# InstAmp.net
KiCad netlist of a schematic drawn in EAGLE
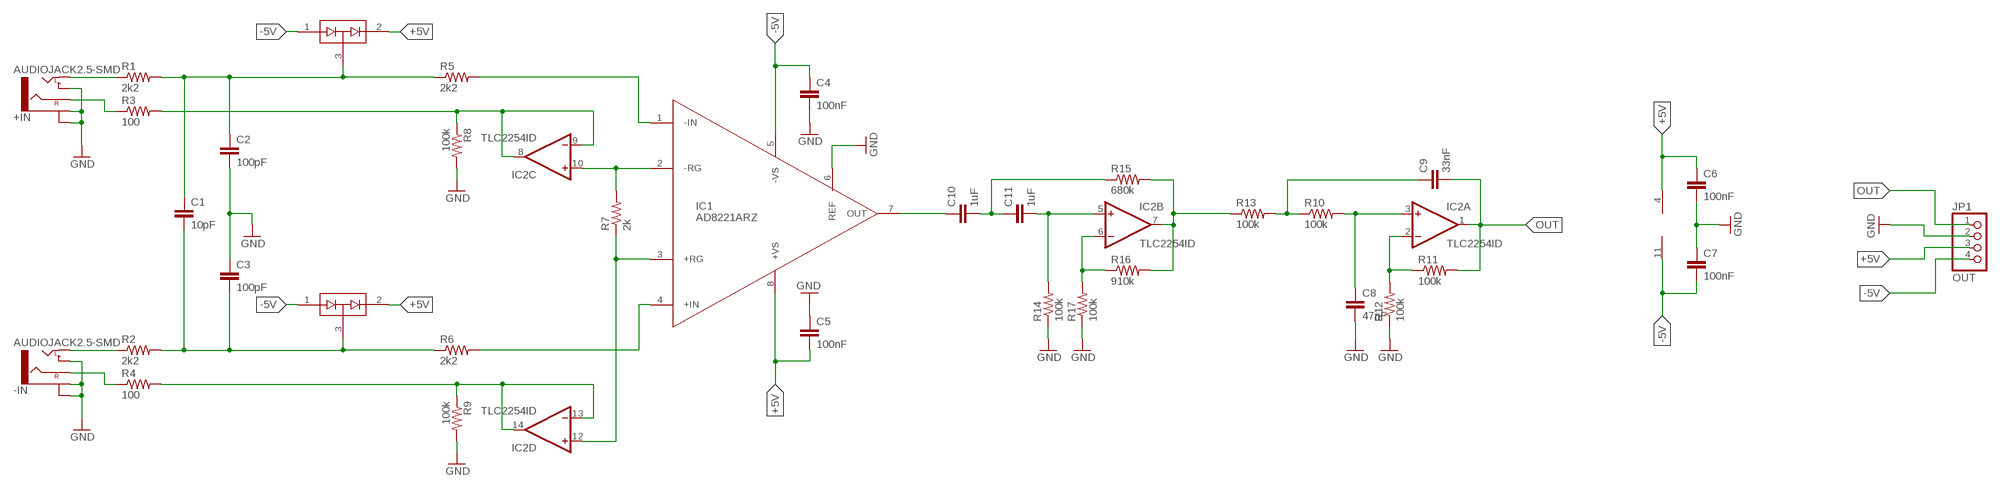
[diagram p0: schematic, sheet 1]

(export (version "E")
  (design (tool "Eeschema 10.0.6"))
  (components
    (comp (ref "+IN")
      (value "AUDIOJACK2.5-SMD")
      (footprint "eagle-import:AUDIOJACK2.5-SMD")
      (libsource (lib "eagle-import") (part "AUDIOJACK2.5-SMD"))
    )
    (comp (ref "-IN")
      (value "AUDIOJACK2.5-SMD")
      (footprint "eagle-import:AUDIOJACK2.5-SMD")
      (libsource (lib "eagle-import") (part "AUDIOJACK2.5-SMD"))
    )
    (comp (ref "C1")
      (value "10pF")
      (footprint "eagle-import:0805")
      (libsource (lib "eagle-import") (part "CAP0805"))
    )
    (comp (ref "C2")
      (value "100pF")
      (footprint "eagle-import:0805")
      (libsource (lib "eagle-import") (part "CAP0805"))
    )
    (comp (ref "C3")
      (value "100pF")
      (footprint "eagle-import:0805")
      (libsource (lib "eagle-import") (part "CAP0805"))
    )
    (comp (ref "C4")
      (value "100nF")
      (footprint "eagle-import:0805")
      (libsource (lib "eagle-import") (part "CAP0805"))
    )
    (comp (ref "C5")
      (value "100nF")
      (footprint "eagle-import:0805")
      (libsource (lib "eagle-import") (part "CAP0805"))
    )
    (comp (ref "C6")
      (value "100nF")
      (footprint "eagle-import:0805")
      (libsource (lib "eagle-import") (part "CAP0805"))
    )
    (comp (ref "C7")
      (value "100nF")
      (footprint "eagle-import:0805")
      (libsource (lib "eagle-import") (part "CAP0805"))
    )
    (comp (ref "C8")
      (value "47nF")
      (footprint "eagle-import:0805")
      (libsource (lib "eagle-import") (part "CAP0805"))
    )
    (comp (ref "C9")
      (value "33nF")
      (footprint "eagle-import:0805")
      (libsource (lib "eagle-import") (part "CAP0805"))
    )
    (comp (ref "C10")
      (value "1uF")
      (footprint "eagle-import:0805")
      (libsource (lib "eagle-import") (part "CAP0805"))
    )
    (comp (ref "C11")
      (value "1uF")
      (footprint "eagle-import:0805")
      (libsource (lib "eagle-import") (part "CAP0805"))
    )
    (comp (ref "D1")
      (value "BAV199")
      (footprint "eagle-import:SOT23")
      (fields (field (name "PROD_ID") "DIO-10647"))
      (libsource (lib "eagle-import") (part "BAV99"))
    )
    (comp (ref "D2")
      (value "BAV199")
      (footprint "eagle-import:SOT23")
      (libsource (lib "eagle-import") (part "BAV99"))
    )
    (comp (ref "IC1")
      (value "AD8221ARZ")
      (footprint "eagle-import:AD8221ARZ")
      (libsource (lib "eagle-import") (part "AD8221ARZ"))
    )
    (comp (ref "IC2")
      (value "TLC2254ID")
      (footprint "eagle-import:SO14")
      (libsource (lib "eagle-import") (part "4AMP_P4+11D"))
    )
    (comp (ref "JP1")
      (value "OUT")
      (footprint "eagle-import:1X04_90")
      (libsource (lib "eagle-import") (part "PINHD-1X4/90"))
    )
    (comp (ref "R1")
      (value "2k2")
      (footprint "eagle-import:0805")
      (libsource (lib "eagle-import") (part "RESISTOR0805-RES"))
    )
    (comp (ref "R2")
      (value "2k2")
      (footprint "eagle-import:0805")
      (libsource (lib "eagle-import") (part "RESISTOR0805-RES"))
    )
    (comp (ref "R3")
      (value "100")
      (footprint "eagle-import:0805")
      (libsource (lib "eagle-import") (part "RESISTOR0805-RES"))
    )
    (comp (ref "R4")
      (value "100")
      (footprint "eagle-import:0805")
      (libsource (lib "eagle-import") (part "RESISTOR0805-RES"))
    )
    (comp (ref "R5")
      (value "2k2")
      (footprint "eagle-import:0805")
      (libsource (lib "eagle-import") (part "RESISTOR0805-RES"))
    )
    (comp (ref "R6")
      (value "2k2")
      (footprint "eagle-import:0805")
      (libsource (lib "eagle-import") (part "RESISTOR0805-RES"))
    )
    (comp (ref "R7")
      (value "2k")
      (footprint "eagle-import:0805")
      (libsource (lib "eagle-import") (part "RESISTOR0805-RES"))
    )
    (comp (ref "R8")
      (value "100k")
      (footprint "eagle-import:0805")
      (libsource (lib "eagle-import") (part "RESISTOR0805-RES"))
    )
    (comp (ref "R9")
      (value "100k")
      (footprint "eagle-import:0805")
      (libsource (lib "eagle-import") (part "RESISTOR0805-RES"))
    )
    (comp (ref "R10")
      (value "100k")
      (footprint "eagle-import:0805")
      (libsource (lib "eagle-import") (part "RESISTOR0805-RES"))
    )
    (comp (ref "R11")
      (value "100k")
      (footprint "eagle-import:0805")
      (libsource (lib "eagle-import") (part "RESISTOR0805-RES"))
    )
    (comp (ref "R12")
      (value "100k")
      (footprint "eagle-import:0805")
      (libsource (lib "eagle-import") (part "RESISTOR0805-RES"))
    )
    (comp (ref "R13")
      (value "100k")
      (footprint "eagle-import:0805")
      (libsource (lib "eagle-import") (part "RESISTOR0805-RES"))
    )
    (comp (ref "R14")
      (value "100k")
      (footprint "eagle-import:0805")
      (libsource (lib "eagle-import") (part "RESISTOR0805-RES"))
    )
    (comp (ref "R15")
      (value "680k")
      (footprint "eagle-import:0805")
      (libsource (lib "eagle-import") (part "RESISTOR0805-RES"))
    )
    (comp (ref "R16")
      (value "910k")
      (footprint "eagle-import:0805")
      (libsource (lib "eagle-import") (part "RESISTOR0805-RES"))
    )
    (comp (ref "R17")
      (value "100k")
      (footprint "eagle-import:0805")
      (libsource (lib "eagle-import") (part "RESISTOR0805-RES"))
    )
  )
  (nets
    (net (code "1") (name "+5V") (class "Default")
      (node (ref "C5") (pin "2") (pinfunction "2_2") (pintype "passive"))
      (node (ref "C6") (pin "1") (pinfunction "1_1") (pintype "passive"))
      (node (ref "D1") (pin "2") (pinfunction "C2_2") (pintype "bidirectional"))
      (node (ref "D2") (pin "2") (pinfunction "C2_2") (pintype "bidirectional"))
      (node (ref "IC1") (pin "8") (pinfunction "+VS_8") (pintype "power_in"))
      (node (ref "IC2") (pin "4") (pinfunction "V+_4") (pintype "power_in"))
      (node (ref "JP1") (pin "3") (pinfunction "3_3") (pintype "passive"))
    )
    (net (code "2") (name "-5V") (class "Default")
      (node (ref "C4") (pin "1") (pinfunction "1_1") (pintype "passive"))
      (node (ref "C7") (pin "2") (pinfunction "2_2") (pintype "passive"))
      (node (ref "D1") (pin "1") (pinfunction "A1_1") (pintype "bidirectional"))
      (node (ref "D2") (pin "1") (pinfunction "A1_1") (pintype "bidirectional"))
      (node (ref "IC1") (pin "5") (pinfunction "-VS_5") (pintype "power_in"))
      (node (ref "IC2") (pin "11") (pinfunction "V-_11") (pintype "power_in"))
      (node (ref "JP1") (pin "4") (pinfunction "4_4") (pintype "passive"))
    )
    (net (code "3") (name "GND") (class "Default")
      (node (ref "+IN") (pin "GND1") (pinfunction "GND1_GND1") (pintype "bidirectional"))
      (node (ref "+IN") (pin "GND2") (pinfunction "GND2_GND2") (pintype "bidirectional"))
      (node (ref "+IN") (pin "SW") (pinfunction "SW_SW") (pintype "bidirectional"))
      (node (ref "-IN") (pin "GND1") (pinfunction "GND1_GND1") (pintype "bidirectional"))
      (node (ref "-IN") (pin "GND2") (pinfunction "GND2_GND2") (pintype "bidirectional"))
      (node (ref "-IN") (pin "SW") (pinfunction "SW_SW") (pintype "bidirectional"))
      (node (ref "C2") (pin "2") (pinfunction "2_2") (pintype "passive"))
      (node (ref "C3") (pin "1") (pinfunction "1_1") (pintype "passive"))
      (node (ref "C4") (pin "2") (pinfunction "2_2") (pintype "passive"))
      (node (ref "C5") (pin "1") (pinfunction "1_1") (pintype "passive"))
      (node (ref "C6") (pin "2") (pinfunction "2_2") (pintype "passive"))
      (node (ref "C7") (pin "1") (pinfunction "1_1") (pintype "passive"))
      (node (ref "C8") (pin "2") (pinfunction "2_2") (pintype "passive"))
      (node (ref "IC1") (pin "6") (pinfunction "REF_6") (pintype "bidirectional"))
      (node (ref "JP1") (pin "2") (pinfunction "2_2") (pintype "passive"))
      (node (ref "R12") (pin "1") (pinfunction "1_1") (pintype "passive"))
      (node (ref "R14") (pin "1") (pinfunction "1_1") (pintype "passive"))
      (node (ref "R17") (pin "1") (pinfunction "1_1") (pintype "passive"))
      (node (ref "R8") (pin "2") (pinfunction "2_2") (pintype "passive"))
      (node (ref "R9") (pin "2") (pinfunction "2_2") (pintype "passive"))
    )
    (net (code "4") (name "Net-(+IN-LEFT)") (class "Default")
      (node (ref "+IN") (pin "L") (pinfunction "LEFT_L") (pintype "bidirectional"))
      (node (ref "R1") (pin "1") (pinfunction "1_1") (pintype "passive"))
    )
    (net (code "5") (name "Net-(+IN-RIGHT)") (class "Default")
      (node (ref "+IN") (pin "R") (pinfunction "RIGHT_R") (pintype "bidirectional"))
      (node (ref "R3") (pin "1") (pinfunction "1_1") (pintype "passive"))
    )
    (net (code "6") (name "Net-(-IN-LEFT)") (class "Default")
      (node (ref "-IN") (pin "L") (pinfunction "LEFT_L") (pintype "bidirectional"))
      (node (ref "R2") (pin "1") (pinfunction "1_1") (pintype "passive"))
    )
    (net (code "7") (name "Net-(-IN-RIGHT)") (class "Default")
      (node (ref "-IN") (pin "R") (pinfunction "RIGHT_R") (pintype "bidirectional"))
      (node (ref "R4") (pin "1") (pinfunction "1_1") (pintype "passive"))
    )
    (net (code "8") (name "Net-(C9-Pad1)") (class "Default")
      (node (ref "C9") (pin "1") (pinfunction "1_1") (pintype "passive"))
      (node (ref "R10") (pin "1") (pinfunction "1_1") (pintype "passive"))
      (node (ref "R13") (pin "2") (pinfunction "2_2") (pintype "passive"))
    )
    (net (code "9") (name "Net-(C10-Pad2)") (class "Default")
      (node (ref "C10") (pin "2") (pinfunction "2_2") (pintype "passive"))
      (node (ref "C11") (pin "1") (pinfunction "1_1") (pintype "passive"))
      (node (ref "R15") (pin "1") (pinfunction "1_1") (pintype "passive"))
    )
    (net (code "10") (name "Net-(D1-COM)") (class "Default")
      (node (ref "C1") (pin "1") (pinfunction "1_1") (pintype "passive"))
      (node (ref "C2") (pin "1") (pinfunction "1_1") (pintype "passive"))
      (node (ref "D1") (pin "3") (pinfunction "COM_3") (pintype "bidirectional"))
      (node (ref "R1") (pin "2") (pinfunction "2_2") (pintype "passive"))
      (node (ref "R5") (pin "1") (pinfunction "1_1") (pintype "passive"))
    )
    (net (code "11") (name "Net-(D2-COM)") (class "Default")
      (node (ref "C1") (pin "2") (pinfunction "2_2") (pintype "passive"))
      (node (ref "C3") (pin "2") (pinfunction "2_2") (pintype "passive"))
      (node (ref "D2") (pin "3") (pinfunction "COM_3") (pintype "bidirectional"))
      (node (ref "R2") (pin "2") (pinfunction "2_2") (pintype "passive"))
      (node (ref "R6") (pin "1") (pinfunction "1_1") (pintype "passive"))
    )
    (net (code "12") (name "Net-(IC1-+IN)") (class "Default")
      (node (ref "IC1") (pin "4") (pinfunction "+IN_4") (pintype "bidirectional"))
      (node (ref "R6") (pin "2") (pinfunction "2_2") (pintype "passive"))
    )
    (net (code "13") (name "Net-(IC1-+RG)") (class "Default")
      (node (ref "IC1") (pin "3") (pinfunction "+RG_3") (pintype "bidirectional"))
      (node (ref "IC2") (pin "12") (pinfunction "+IN_12") (pintype "input"))
      (node (ref "R7") (pin "1") (pinfunction "1_1") (pintype "passive"))
    )
    (net (code "14") (name "Net-(IC1--IN)") (class "Default")
      (node (ref "IC1") (pin "1") (pinfunction "-IN_1") (pintype "bidirectional"))
      (node (ref "R5") (pin "2") (pinfunction "2_2") (pintype "passive"))
    )
    (net (code "15") (name "Net-(IC1--RG)") (class "Default")
      (node (ref "IC1") (pin "2") (pinfunction "-RG_2") (pintype "bidirectional"))
      (node (ref "IC2") (pin "10") (pinfunction "+IN_10") (pintype "input"))
      (node (ref "R7") (pin "2") (pinfunction "2_2") (pintype "passive"))
    )
    (net (code "16") (name "Net-(IC1-OUT)") (class "Default")
      (node (ref "C10") (pin "1") (pinfunction "1_1") (pintype "passive"))
      (node (ref "IC1") (pin "7") (pinfunction "OUT_7") (pintype "bidirectional"))
    )
    (net (code "17") (name "Net-(IC2A-+IN)") (class "Default")
      (node (ref "C8") (pin "1") (pinfunction "1_1") (pintype "passive"))
      (node (ref "IC2") (pin "3") (pinfunction "+IN_3") (pintype "input"))
      (node (ref "R10") (pin "2") (pinfunction "2_2") (pintype "passive"))
    )
    (net (code "18") (name "Net-(IC2A--IN)") (class "Default")
      (node (ref "IC2") (pin "2") (pinfunction "-IN_2") (pintype "input"))
      (node (ref "R11") (pin "1") (pinfunction "1_1") (pintype "passive"))
      (node (ref "R12") (pin "2") (pinfunction "2_2") (pintype "passive"))
    )
    (net (code "19") (name "Net-(IC2B-+IN)") (class "Default")
      (node (ref "C11") (pin "2") (pinfunction "2_2") (pintype "passive"))
      (node (ref "IC2") (pin "5") (pinfunction "+IN_5") (pintype "input"))
      (node (ref "R14") (pin "2") (pinfunction "2_2") (pintype "passive"))
    )
    (net (code "20") (name "Net-(IC2B--IN)") (class "Default")
      (node (ref "IC2") (pin "6") (pinfunction "-IN_6") (pintype "input"))
      (node (ref "R16") (pin "1") (pinfunction "1_1") (pintype "passive"))
      (node (ref "R17") (pin "2") (pinfunction "2_2") (pintype "passive"))
    )
    (net (code "21") (name "Net-(IC2B-OUT)") (class "Default")
      (node (ref "IC2") (pin "7") (pinfunction "OUT_7") (pintype "output"))
      (node (ref "R13") (pin "1") (pinfunction "1_1") (pintype "passive"))
      (node (ref "R15") (pin "2") (pinfunction "2_2") (pintype "passive"))
      (node (ref "R16") (pin "2") (pinfunction "2_2") (pintype "passive"))
    )
    (net (code "22") (name "Net-(IC2C--IN)") (class "Default")
      (node (ref "IC2") (pin "8") (pinfunction "OUT_8") (pintype "output"))
      (node (ref "IC2") (pin "9") (pinfunction "-IN_9") (pintype "input"))
      (node (ref "R3") (pin "2") (pinfunction "2_2") (pintype "passive"))
      (node (ref "R8") (pin "1") (pinfunction "1_1") (pintype "passive"))
    )
    (net (code "23") (name "Net-(IC2D--IN)") (class "Default")
      (node (ref "IC2") (pin "13") (pinfunction "-IN_13") (pintype "input"))
      (node (ref "IC2") (pin "14") (pinfunction "OUT_14") (pintype "output"))
      (node (ref "R4") (pin "2") (pinfunction "2_2") (pintype "passive"))
      (node (ref "R9") (pin "1") (pinfunction "1_1") (pintype "passive"))
    )
    (net (code "24") (name "OUT") (class "Default")
      (node (ref "C9") (pin "2") (pinfunction "2_2") (pintype "passive"))
      (node (ref "IC2") (pin "1") (pinfunction "OUT_1") (pintype "output"))
      (node (ref "JP1") (pin "1") (pinfunction "1_1") (pintype "passive"))
      (node (ref "R11") (pin "2") (pinfunction "2_2") (pintype "passive"))
    )
  )
)
